# SCH_RelayModule.net
KiCad netlist of a schematic drawn in EasyEDA
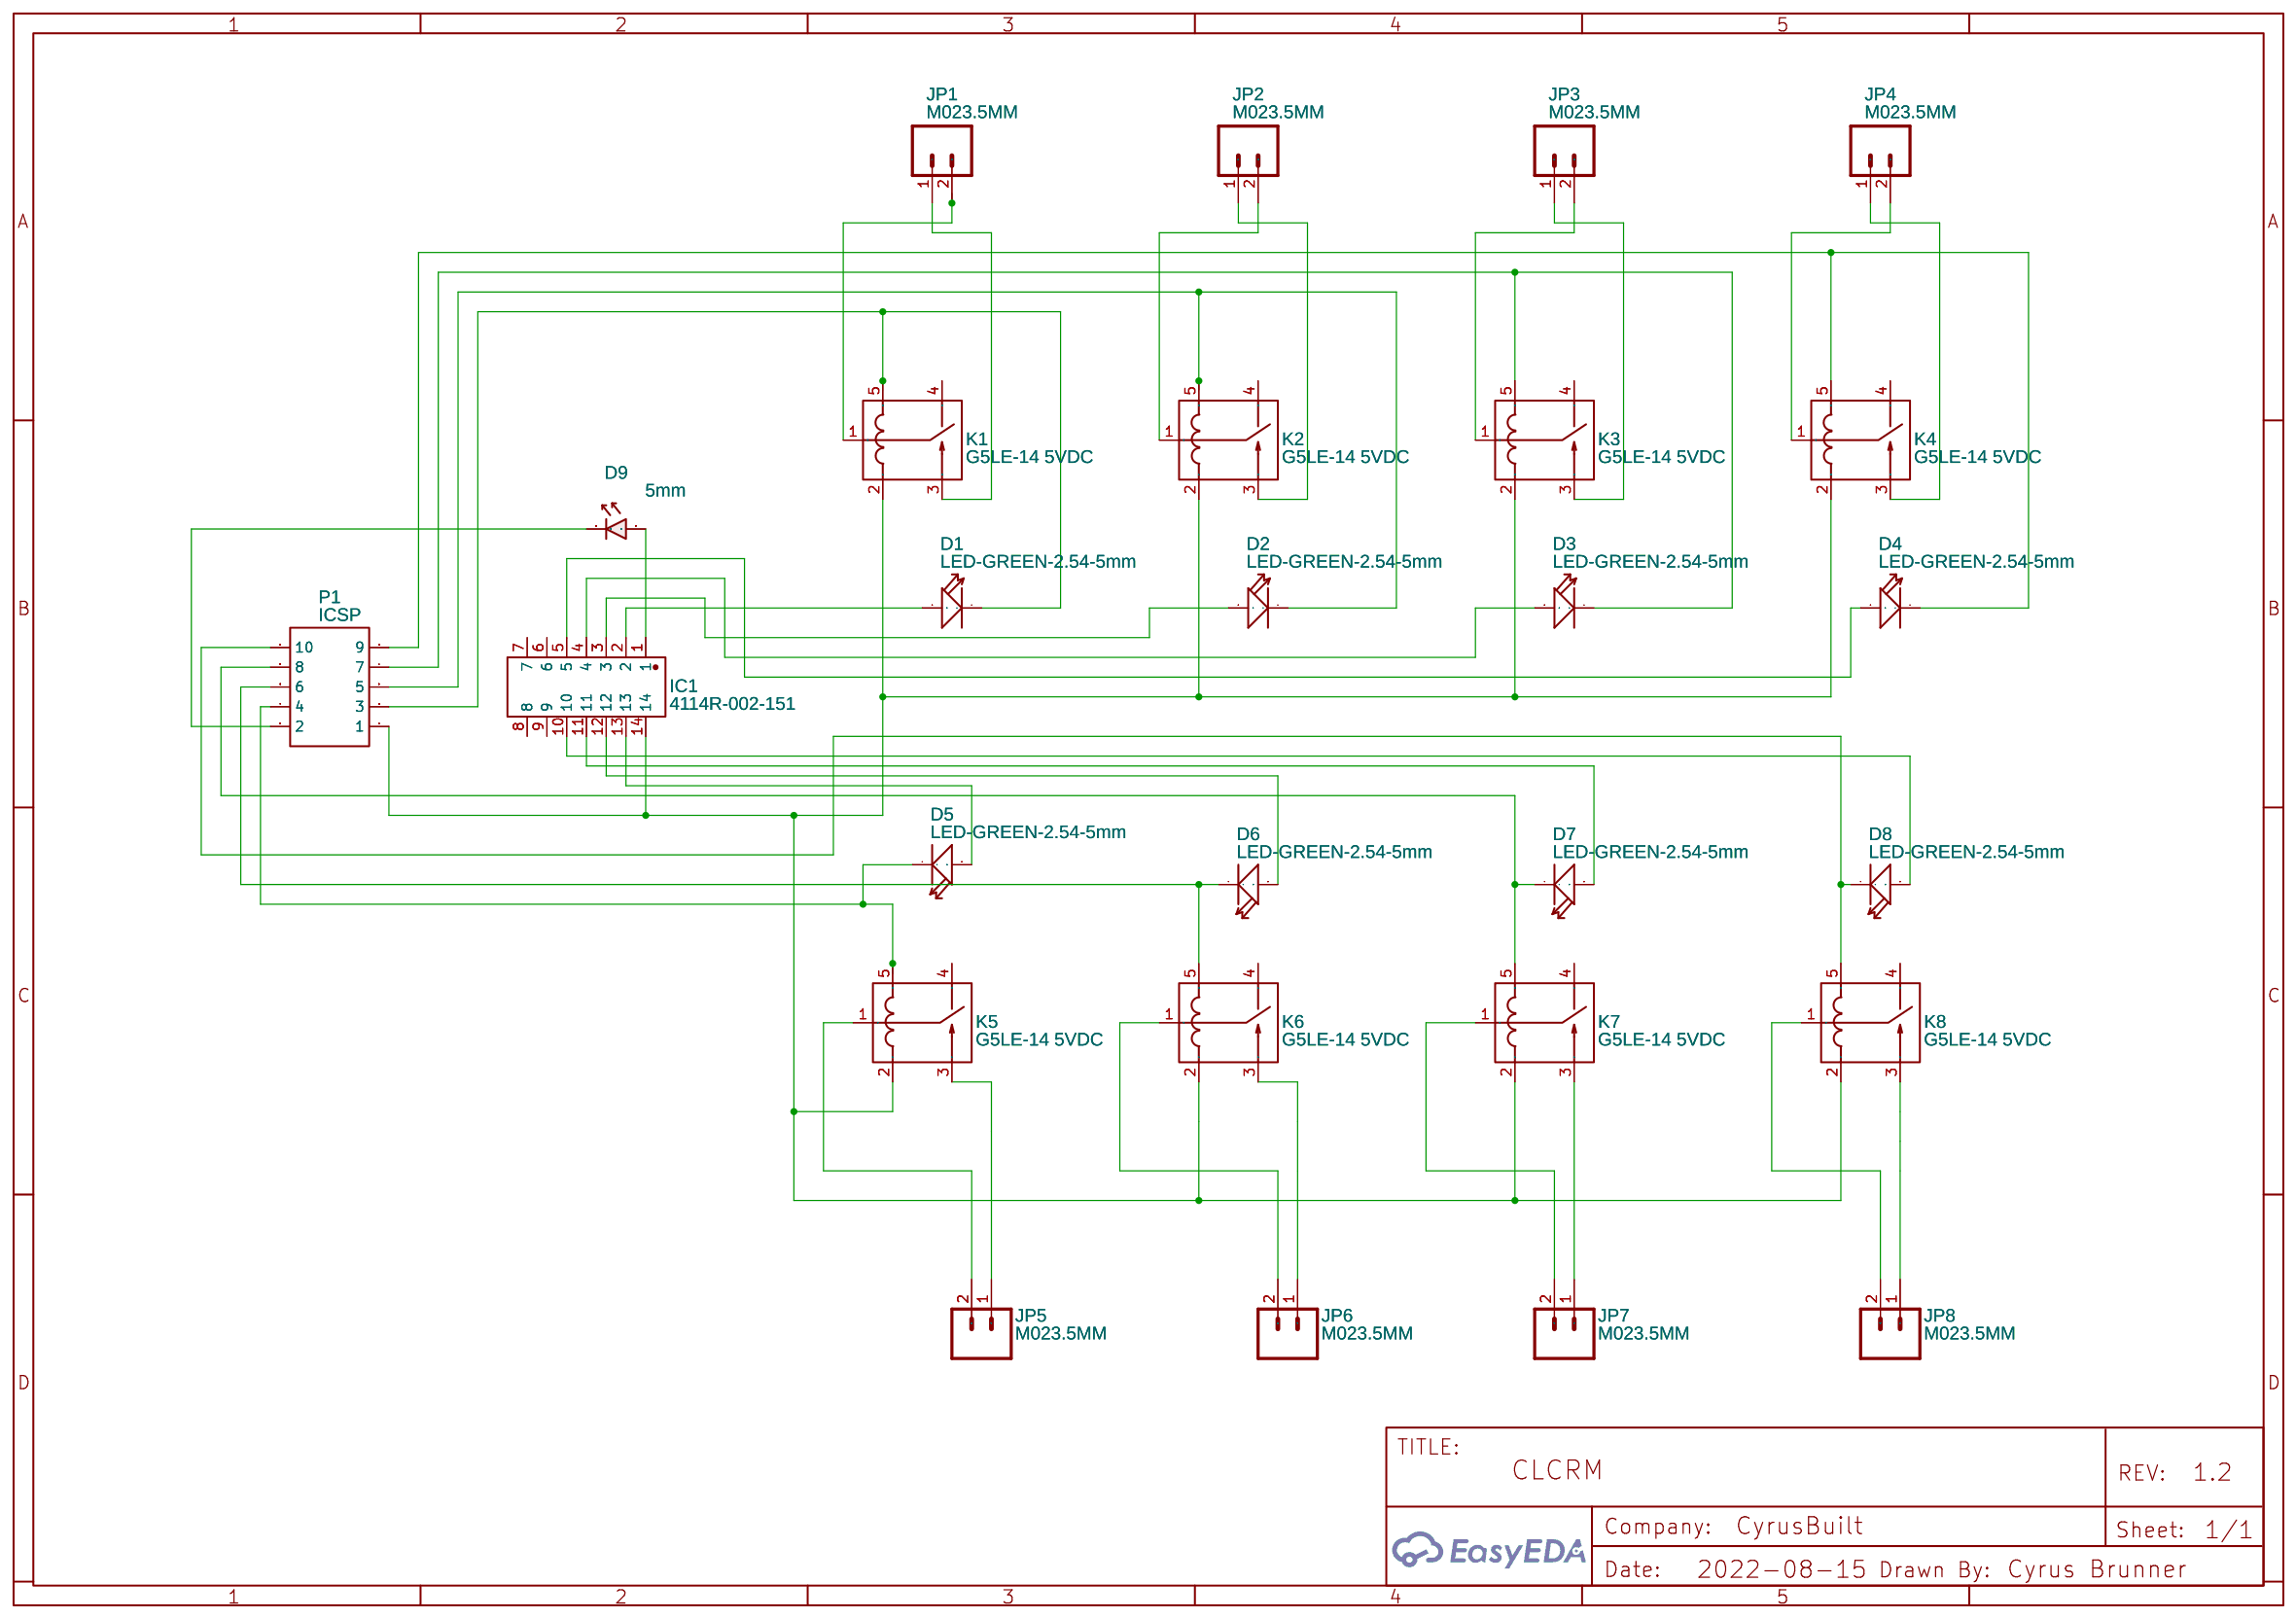
[diagram p0: schematic sheet]

(export (version "E")
  (design (tool "Eeschema 10.0.6"))
  (components
    (comp (ref "D1")
      (value "LED-GREEN-2.54-5mm")
      (fields (field (name "BOM_Manufacturer Part") "503UOC"))
      (libsource (lib "") (part "LED-GREEN-2.54-5mm_1"))
    )
    (comp (ref "D2")
      (value "LED-GREEN-2.54-5mm")
      (fields (field (name "BOM_Manufacturer Part") "503UOC"))
      (libsource (lib "") (part "LED-GREEN-2.54-5mm_1"))
    )
    (comp (ref "D3")
      (value "LED-GREEN-2.54-5mm")
      (fields (field (name "BOM_Manufacturer Part") "503UOC"))
      (libsource (lib "") (part "LED-GREEN-2.54-5mm_1"))
    )
    (comp (ref "D4")
      (value "LED-GREEN-2.54-5mm")
      (fields (field (name "BOM_Manufacturer Part") "503UOC"))
      (libsource (lib "") (part "LED-GREEN-2.54-5mm_1"))
    )
    (comp (ref "D5")
      (value "LED-GREEN-2.54-5mm")
      (fields (field (name "BOM_Manufacturer Part") "503UOC"))
      (libsource (lib "") (part "LED-GREEN-2.54-5mm"))
    )
    (comp (ref "D6")
      (value "LED-GREEN-2.54-5mm")
      (fields (field (name "BOM_Manufacturer Part") "503UOC"))
      (libsource (lib "") (part "LED-GREEN-2.54-5mm"))
    )
    (comp (ref "D7")
      (value "LED-GREEN-2.54-5mm")
      (fields (field (name "BOM_Manufacturer Part") "503UOC"))
      (libsource (lib "") (part "LED-GREEN-2.54-5mm"))
    )
    (comp (ref "D8")
      (value "LED-GREEN-2.54-5mm")
      (fields (field (name "BOM_Manufacturer Part") "503UOC"))
      (libsource (lib "") (part "LED-GREEN-2.54-5mm"))
    )
    (comp (ref "D9")
      (value "5mm")
      (fields (field (name "BOM_Manufacturer Part") "L-1503EC") (field (name "BOM_Supplier Part") "1003201"))
      (libsource (lib "") (part "RED LED"))
    )
    (comp (ref "IC1")
      (value "4114R-002-151")
      (fields
        (field (name "BOM_Manufacturer Part") "100-143-200-1001-00")
        (field (name "BOM_Supplier Part") "C2846065")
      )
      (libsource (lib "") (part "100-143-200-1001-00"))
    )
    (comp (ref "JP1") (value "M023.5MM") (libsource (lib "") (part "M023.5MM")))
    (comp (ref "JP2") (value "M023.5MM") (libsource (lib "") (part "M023.5MM")))
    (comp (ref "JP3") (value "M023.5MM") (libsource (lib "") (part "M023.5MM")))
    (comp (ref "JP4") (value "M023.5MM") (libsource (lib "") (part "M023.5MM")))
    (comp (ref "JP5") (value "M023.5MM") (libsource (lib "") (part "M023.5MM_1")))
    (comp (ref "JP6") (value "M023.5MM") (libsource (lib "") (part "M023.5MM_1")))
    (comp (ref "JP7") (value "M023.5MM") (libsource (lib "") (part "M023.5MM_1")))
    (comp (ref "JP8") (value "M023.5MM") (libsource (lib "") (part "M023.5MM_1")))
    (comp (ref "K1")
      (value "G5LE-14 5VDC")
      (fields (field (name "BOM_Supplier Part") "C116963"))
      (libsource (lib "") (part "G5LE-14 5VDC"))
    )
    (comp (ref "K2")
      (value "G5LE-14 5VDC")
      (fields (field (name "BOM_Supplier Part") "C116963"))
      (libsource (lib "") (part "G5LE-14 5VDC"))
    )
    (comp (ref "K3")
      (value "G5LE-14 5VDC")
      (fields (field (name "BOM_Supplier Part") "C116963"))
      (libsource (lib "") (part "G5LE-14 5VDC"))
    )
    (comp (ref "K4")
      (value "G5LE-14 5VDC")
      (fields (field (name "BOM_Supplier Part") "C116963"))
      (libsource (lib "") (part "G5LE-14 5VDC"))
    )
    (comp (ref "K5")
      (value "G5LE-14 5VDC")
      (fields (field (name "BOM_Supplier Part") "C116963"))
      (libsource (lib "") (part "G5LE-14 5VDC"))
    )
    (comp (ref "K6")
      (value "G5LE-14 5VDC")
      (fields (field (name "BOM_Supplier Part") "C116963"))
      (libsource (lib "") (part "G5LE-14 5VDC"))
    )
    (comp (ref "K7")
      (value "G5LE-14 5VDC")
      (fields (field (name "BOM_Supplier Part") "C116963"))
      (libsource (lib "") (part "G5LE-14 5VDC"))
    )
    (comp (ref "K8")
      (value "G5LE-14 5VDC")
      (fields (field (name "BOM_Supplier Part") "C116963"))
      (libsource (lib "") (part "G5LE-14 5VDC"))
    )
    (comp (ref "P1")
      (value "ICSP")
      (fields
        (field (name "BOM_Manufacturer Part") "IDC Box 2.54mm 2X5P")
        (field (name "BOM_Supplier Part") "C5665")
      )
      (libsource (lib "") (part "ICSP"))
    )
  )
  (nets
    (net (code "1") (name "Net-(D1-Pad+)") (class "Default")
      (node (ref "D1") (pin "+") (pinfunction "+_+") (pintype "unspecified"))
      (node (ref "IC1") (pin "2") (pinfunction "2_2") (pintype "unspecified"))
    )
    (net (code "2") (name "Net-(D1-Pad-)") (class "Default")
      (node (ref "D1") (pin "-") (pinfunction "-_-") (pintype "unspecified"))
      (node (ref "K1") (pin "5") (pinfunction "5_5") (pintype "unspecified"))
      (node (ref "P1") (pin "3") (pinfunction "3_3") (pintype "unspecified"))
    )
    (net (code "3") (name "Net-(D2-Pad+)") (class "Default")
      (node (ref "D2") (pin "+") (pinfunction "+_+") (pintype "unspecified"))
      (node (ref "IC1") (pin "3") (pinfunction "3_3") (pintype "unspecified"))
    )
    (net (code "4") (name "Net-(D2-Pad-)") (class "Default")
      (node (ref "D2") (pin "-") (pinfunction "-_-") (pintype "unspecified"))
      (node (ref "K2") (pin "5") (pinfunction "5_5") (pintype "unspecified"))
      (node (ref "P1") (pin "5") (pinfunction "5_5") (pintype "unspecified"))
    )
    (net (code "5") (name "Net-(D3-Pad+)") (class "Default")
      (node (ref "D3") (pin "+") (pinfunction "+_+") (pintype "unspecified"))
      (node (ref "IC1") (pin "4") (pinfunction "4_4") (pintype "unspecified"))
    )
    (net (code "6") (name "Net-(D3-Pad-)") (class "Default")
      (node (ref "D3") (pin "-") (pinfunction "-_-") (pintype "unspecified"))
      (node (ref "K3") (pin "5") (pinfunction "5_5") (pintype "unspecified"))
      (node (ref "P1") (pin "7") (pinfunction "7_7") (pintype "unspecified"))
    )
    (net (code "7") (name "Net-(D4-Pad+)") (class "Default")
      (node (ref "D4") (pin "+") (pinfunction "+_+") (pintype "unspecified"))
      (node (ref "IC1") (pin "5") (pinfunction "5_5") (pintype "unspecified"))
    )
    (net (code "8") (name "Net-(D4-Pad-)") (class "Default")
      (node (ref "D4") (pin "-") (pinfunction "-_-") (pintype "unspecified"))
      (node (ref "K4") (pin "5") (pinfunction "5_5") (pintype "unspecified"))
      (node (ref "P1") (pin "9") (pinfunction "9_9") (pintype "unspecified"))
    )
    (net (code "9") (name "Net-(D5-Pad+)") (class "Default")
      (node (ref "D5") (pin "+") (pinfunction "+_+") (pintype "unspecified"))
      (node (ref "IC1") (pin "13") (pinfunction "13_13") (pintype "unspecified"))
    )
    (net (code "10") (name "Net-(D5-Pad-)") (class "Default")
      (node (ref "D5") (pin "-") (pinfunction "-_-") (pintype "unspecified"))
      (node (ref "K5") (pin "5") (pinfunction "5_5") (pintype "unspecified"))
      (node (ref "P1") (pin "4") (pinfunction "4_4") (pintype "unspecified"))
    )
    (net (code "11") (name "Net-(D6-Pad+)") (class "Default")
      (node (ref "D6") (pin "+") (pinfunction "+_+") (pintype "unspecified"))
      (node (ref "IC1") (pin "12") (pinfunction "12_12") (pintype "unspecified"))
    )
    (net (code "12") (name "Net-(D6-Pad-)") (class "Default")
      (node (ref "D6") (pin "-") (pinfunction "-_-") (pintype "unspecified"))
      (node (ref "K6") (pin "5") (pinfunction "5_5") (pintype "unspecified"))
      (node (ref "P1") (pin "6") (pinfunction "6_6") (pintype "unspecified"))
    )
    (net (code "13") (name "Net-(D7-Pad+)") (class "Default")
      (node (ref "D7") (pin "+") (pinfunction "+_+") (pintype "unspecified"))
      (node (ref "IC1") (pin "11") (pinfunction "11_11") (pintype "unspecified"))
    )
    (net (code "14") (name "Net-(D7-Pad-)") (class "Default")
      (node (ref "D7") (pin "-") (pinfunction "-_-") (pintype "unspecified"))
      (node (ref "K7") (pin "5") (pinfunction "5_5") (pintype "unspecified"))
      (node (ref "P1") (pin "8") (pinfunction "8_8") (pintype "unspecified"))
    )
    (net (code "15") (name "Net-(D8-Pad+)") (class "Default")
      (node (ref "D8") (pin "+") (pinfunction "+_+") (pintype "unspecified"))
      (node (ref "IC1") (pin "10") (pinfunction "10_10") (pintype "unspecified"))
    )
    (net (code "16") (name "Net-(D8-Pad-)") (class "Default")
      (node (ref "D8") (pin "-") (pinfunction "-_-") (pintype "unspecified"))
      (node (ref "K8") (pin "5") (pinfunction "5_5") (pintype "unspecified"))
      (node (ref "P1") (pin "10") (pinfunction "10_10") (pintype "unspecified"))
    )
    (net (code "17") (name "Net-(D9-Pad1)") (class "Default")
      (node (ref "D9") (pin "1") (pinfunction "1_1") (pintype "unspecified"))
      (node (ref "IC1") (pin "1") (pinfunction "1_1") (pintype "unspecified"))
    )
    (net (code "18") (name "Net-(D9-Pad2)") (class "Default")
      (node (ref "D9") (pin "2") (pinfunction "2_2") (pintype "unspecified"))
      (node (ref "P1") (pin "2") (pinfunction "2_2") (pintype "unspecified"))
    )
    (net (code "19") (name "Net-(IC1-Pad14)") (class "Default")
      (node (ref "IC1") (pin "14") (pinfunction "14_14") (pintype "unspecified"))
      (node (ref "K1") (pin "2") (pinfunction "2_2") (pintype "unspecified"))
      (node (ref "K2") (pin "2") (pinfunction "2_2") (pintype "unspecified"))
      (node (ref "K3") (pin "2") (pinfunction "2_2") (pintype "unspecified"))
      (node (ref "K4") (pin "2") (pinfunction "2_2") (pintype "unspecified"))
      (node (ref "K5") (pin "2") (pinfunction "2_2") (pintype "unspecified"))
      (node (ref "K6") (pin "2") (pinfunction "2_2") (pintype "unspecified"))
      (node (ref "K7") (pin "2") (pinfunction "2_2") (pintype "unspecified"))
      (node (ref "K8") (pin "2") (pinfunction "2_2") (pintype "unspecified"))
      (node (ref "P1") (pin "1") (pinfunction "1_1") (pintype "unspecified"))
    )
    (net (code "20") (name "Net-(JP1-Pad1)") (class "Default")
      (node (ref "JP1") (pin "1") (pinfunction "1_1") (pintype "bidirectional"))
      (node (ref "K1") (pin "3") (pinfunction "3_3") (pintype "unspecified"))
    )
    (net (code "21") (name "Net-(JP1-Pad2)") (class "Default")
      (node (ref "JP1") (pin "2") (pinfunction "2_2") (pintype "bidirectional"))
      (node (ref "K1") (pin "1") (pinfunction "1_1") (pintype "unspecified"))
    )
    (net (code "22") (name "Net-(JP2-Pad1)") (class "Default")
      (node (ref "JP2") (pin "1") (pinfunction "1_1") (pintype "bidirectional"))
      (node (ref "K2") (pin "3") (pinfunction "3_3") (pintype "unspecified"))
    )
    (net (code "23") (name "Net-(JP2-Pad2)") (class "Default")
      (node (ref "JP2") (pin "2") (pinfunction "2_2") (pintype "bidirectional"))
      (node (ref "K2") (pin "1") (pinfunction "1_1") (pintype "unspecified"))
    )
    (net (code "24") (name "Net-(JP3-Pad1)") (class "Default")
      (node (ref "JP3") (pin "1") (pinfunction "1_1") (pintype "bidirectional"))
      (node (ref "K3") (pin "3") (pinfunction "3_3") (pintype "unspecified"))
    )
    (net (code "25") (name "Net-(JP3-Pad2)") (class "Default")
      (node (ref "JP3") (pin "2") (pinfunction "2_2") (pintype "bidirectional"))
      (node (ref "K3") (pin "1") (pinfunction "1_1") (pintype "unspecified"))
    )
    (net (code "26") (name "Net-(JP4-Pad1)") (class "Default")
      (node (ref "JP4") (pin "1") (pinfunction "1_1") (pintype "bidirectional"))
      (node (ref "K4") (pin "3") (pinfunction "3_3") (pintype "unspecified"))
    )
    (net (code "27") (name "Net-(JP4-Pad2)") (class "Default")
      (node (ref "JP4") (pin "2") (pinfunction "2_2") (pintype "bidirectional"))
      (node (ref "K4") (pin "1") (pinfunction "1_1") (pintype "unspecified"))
    )
    (net (code "28") (name "Net-(JP5-Pad1)") (class "Default")
      (node (ref "JP5") (pin "1") (pinfunction "1_1") (pintype "bidirectional"))
      (node (ref "K5") (pin "3") (pinfunction "3_3") (pintype "unspecified"))
    )
    (net (code "29") (name "Net-(JP5-Pad2)") (class "Default")
      (node (ref "JP5") (pin "2") (pinfunction "2_2") (pintype "bidirectional"))
      (node (ref "K5") (pin "1") (pinfunction "1_1") (pintype "unspecified"))
    )
    (net (code "30") (name "Net-(JP6-Pad1)") (class "Default")
      (node (ref "JP6") (pin "1") (pinfunction "1_1") (pintype "bidirectional"))
      (node (ref "K6") (pin "3") (pinfunction "3_3") (pintype "unspecified"))
    )
    (net (code "31") (name "Net-(JP6-Pad2)") (class "Default")
      (node (ref "JP6") (pin "2") (pinfunction "2_2") (pintype "bidirectional"))
      (node (ref "K6") (pin "1") (pinfunction "1_1") (pintype "unspecified"))
    )
    (net (code "32") (name "Net-(JP7-Pad1)") (class "Default")
      (node (ref "JP7") (pin "1") (pinfunction "1_1") (pintype "bidirectional"))
      (node (ref "K7") (pin "3") (pinfunction "3_3") (pintype "unspecified"))
    )
    (net (code "33") (name "Net-(JP7-Pad2)") (class "Default")
      (node (ref "JP7") (pin "2") (pinfunction "2_2") (pintype "bidirectional"))
      (node (ref "K7") (pin "1") (pinfunction "1_1") (pintype "unspecified"))
    )
    (net (code "34") (name "Net-(JP8-Pad1)") (class "Default")
      (node (ref "JP8") (pin "1") (pinfunction "1_1") (pintype "bidirectional"))
      (node (ref "K8") (pin "3") (pinfunction "3_3") (pintype "unspecified"))
    )
    (net (code "35") (name "Net-(JP8-Pad2)") (class "Default")
      (node (ref "JP8") (pin "2") (pinfunction "2_2") (pintype "bidirectional"))
      (node (ref "K8") (pin "1") (pinfunction "1_1") (pintype "unspecified"))
    )
    (net (code "36") (name "unconnected-(IC1-Pad6)") (class "Default")
      (node (ref "IC1") (pin "6") (pinfunction "6_6") (pintype "unspecified"))
    )
    (net (code "37") (name "unconnected-(IC1-Pad7)") (class "Default")
      (node (ref "IC1") (pin "7") (pinfunction "7_7") (pintype "unspecified"))
    )
    (net (code "38") (name "unconnected-(IC1-Pad8)") (class "Default")
      (node (ref "IC1") (pin "8") (pinfunction "8_8") (pintype "unspecified"))
    )
    (net (code "39") (name "unconnected-(IC1-Pad9)") (class "Default")
      (node (ref "IC1") (pin "9") (pinfunction "9_9") (pintype "unspecified"))
    )
    (net (code "40") (name "unconnected-(K1-Pad4)") (class "Default")
      (node (ref "K1") (pin "4") (pinfunction "4_4") (pintype "unspecified"))
    )
    (net (code "41") (name "unconnected-(K2-Pad4)") (class "Default")
      (node (ref "K2") (pin "4") (pinfunction "4_4") (pintype "unspecified"))
    )
    (net (code "42") (name "unconnected-(K3-Pad4)") (class "Default")
      (node (ref "K3") (pin "4") (pinfunction "4_4") (pintype "unspecified"))
    )
    (net (code "43") (name "unconnected-(K4-Pad4)") (class "Default")
      (node (ref "K4") (pin "4") (pinfunction "4_4") (pintype "unspecified"))
    )
    (net (code "44") (name "unconnected-(K5-Pad4)") (class "Default")
      (node (ref "K5") (pin "4") (pinfunction "4_4") (pintype "unspecified"))
    )
    (net (code "45") (name "unconnected-(K6-Pad4)") (class "Default")
      (node (ref "K6") (pin "4") (pinfunction "4_4") (pintype "unspecified"))
    )
    (net (code "46") (name "unconnected-(K7-Pad4)") (class "Default")
      (node (ref "K7") (pin "4") (pinfunction "4_4") (pintype "unspecified"))
    )
    (net (code "47") (name "unconnected-(K8-Pad4)") (class "Default")
      (node (ref "K8") (pin "4") (pinfunction "4_4") (pintype "unspecified"))
    )
  )
)
